# Taiwan_Arduino.net
KiCad netlist of a schematic drawn in EAGLE
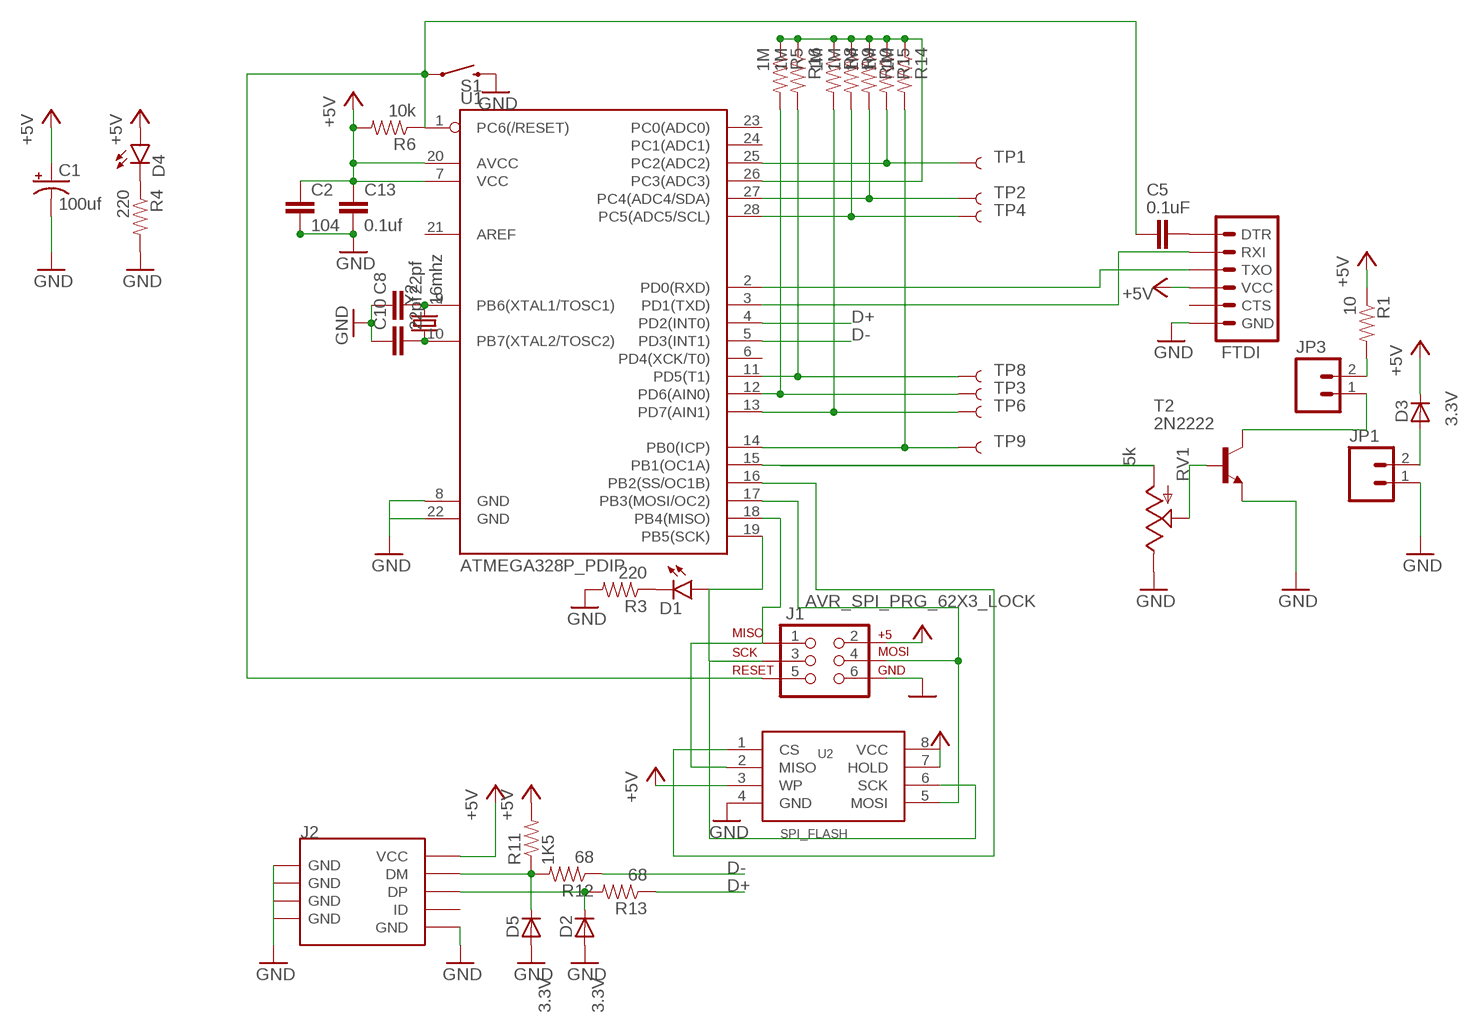
[diagram p0: schematic, sheet 1]

(export (version "E")
  (design (tool "Eeschema 10.0.6"))
  (components
    (comp (ref "C1")
      (value "100uf")
      (footprint "eagle-import:E2,5-5")
      (libsource (lib "eagle-import") (part "CPOL-USE2.5-5"))
    )
    (comp (ref "C2")
      (value "104")
      (footprint "eagle-import:CAP-PTH-5MM")
      (libsource (lib "eagle-import") (part "CAPPTH1"))
    )
    (comp (ref "C5")
      (value "0.1uF")
      (footprint "eagle-import:CAP-PTH-5MM")
      (libsource (lib "eagle-import") (part "CAPPTH1"))
    )
    (comp (ref "C8")
      (value "22pf")
      (footprint "eagle-import:CAP-PTH-5MM")
      (libsource (lib "eagle-import") (part "CAPPTH1"))
    )
    (comp (ref "C10")
      (value "22pf")
      (footprint "eagle-import:CAP-PTH-5MM")
      (libsource (lib "eagle-import") (part "CAPPTH1"))
    )
    (comp (ref "C13")
      (value "0.1uf")
      (footprint "eagle-import:CAP-PTH-5MM")
      (libsource (lib "eagle-import") (part "CAPPTH1"))
    )
    (comp (ref "D1")
      (value "LED3MM")
      (footprint "eagle-import:LED3MM")
      (libsource (lib "eagle-import") (part "LED3MM"))
    )
    (comp (ref "D2")
      (value "3.3V")
      (footprint "eagle-import:0204V")
      (libsource (lib "eagle-import") (part "DIODE-VERTDIODE_SM_VERT"))
    )
    (comp (ref "D3")
      (value "3.3V")
      (footprint "eagle-import:0204V")
      (libsource (lib "eagle-import") (part "DIODE-VERTDIODE_SM_VERT"))
    )
    (comp (ref "D4")
      (value "LED3MM")
      (footprint "eagle-import:LED3MM")
      (libsource (lib "eagle-import") (part "LED3MM"))
    )
    (comp (ref "D5")
      (value "3.3V")
      (footprint "eagle-import:0204V")
      (libsource (lib "eagle-import") (part "DIODE-VERTDIODE_SM_VERT"))
    )
    (comp (ref "FTDI")
      (value "ARDUINO_SERIAL_PROGRAMLOCK")
      (footprint "eagle-import:1X06_LOCK")
      (libsource (lib "eagle-import") (part "ARDUINO_SERIAL_PROGRAMLOCK"))
    )
    (comp (ref "J1")
      (value "AVR_SPI_PRG_62X3_LOCK")
      (footprint "eagle-import:2X3_LOCK")
      (libsource (lib "eagle-import") (part "AVR_SPI_PRG_62X3_LOCK"))
    )
    (comp (ref "J2")
      (value "USB-MINIUSB-5P-TH")
      (footprint "eagle-import:MINI-5P")
      (libsource (lib "eagle-import") (part "USB-MINIUSB-5P-TH"))
    )
    (comp (ref "JP1")
      (value "Battery")
      (footprint "eagle-import:1X02")
      (libsource (lib "eagle-import") (part "M02PTH"))
    )
    (comp (ref "JP3")
      (value "M021X02_NO_SILK")
      (footprint "eagle-import:1X02_NO_SILK")
      (libsource (lib "eagle-import") (part "M021X02_NO_SILK"))
    )
    (comp (ref "R1")
      (value "10")
      (footprint "eagle-import:AXIAL-0.1")
      (libsource (lib "eagle-import") (part "RESISTORPTH-1/4W-VERT"))
    )
    (comp (ref "R3")
      (value "220")
      (footprint "eagle-import:AXIAL-0.1")
      (libsource (lib "eagle-import") (part "RESISTORPTH-1/4W-VERT"))
    )
    (comp (ref "R4")
      (value "220")
      (footprint "eagle-import:AXIAL-0.1")
      (libsource (lib "eagle-import") (part "RESISTORPTH-1/4W-VERT"))
    )
    (comp (ref "R5")
      (value "1M")
      (footprint "eagle-import:AXIAL-0.1")
      (libsource (lib "eagle-import") (part "RESISTORPTH-1/4W-VERT"))
    )
    (comp (ref "R6")
      (value "10k")
      (footprint "eagle-import:AXIAL-0.1")
      (libsource (lib "eagle-import") (part "RESISTORPTH-1/4W-VERT"))
    )
    (comp (ref "R8")
      (value "1M")
      (footprint "eagle-import:AXIAL-0.1")
      (libsource (lib "eagle-import") (part "RESISTORPTH-1/4W-VERT"))
    )
    (comp (ref "R9")
      (value "1M")
      (footprint "eagle-import:AXIAL-0.1")
      (libsource (lib "eagle-import") (part "RESISTORPTH-1/4W-VERT"))
    )
    (comp (ref "R10")
      (value "1M")
      (footprint "eagle-import:AXIAL-0.1")
      (libsource (lib "eagle-import") (part "RESISTORPTH-1/4W-VERT"))
    )
    (comp (ref "R11")
      (value "1K5")
      (footprint "eagle-import:AXIAL-0.1")
      (libsource (lib "eagle-import") (part "RESISTORPTH-1/4W-VERT"))
    )
    (comp (ref "R12")
      (value "68")
      (footprint "eagle-import:AXIAL-0.1")
      (libsource (lib "eagle-import") (part "RESISTORPTH-1/4W-VERT"))
    )
    (comp (ref "R13")
      (value "68")
      (footprint "eagle-import:AXIAL-0.1")
      (libsource (lib "eagle-import") (part "RESISTORPTH-1/4W-VERT"))
    )
    (comp (ref "R14")
      (value "1M")
      (footprint "eagle-import:AXIAL-0.4")
      (libsource (lib "eagle-import") (part "RESISTORPTH-1/4W"))
    )
    (comp (ref "R15")
      (value "1M")
      (footprint "eagle-import:AXIAL-0.1")
      (libsource (lib "eagle-import") (part "RESISTORPTH-1/4W-VERT"))
    )
    (comp (ref "R16")
      (value "1M")
      (footprint "eagle-import:AXIAL-0.1")
      (libsource (lib "eagle-import") (part "RESISTORPTH-1/4W-VERT"))
    )
    (comp (ref "RV1")
      (value "5k")
      (footprint "eagle-import:ALPS_POT")
      (libsource (lib "eagle-import") (part "POT"))
    )
    (comp (ref "S1")
      (value "SWITCH-MOMENTARY-2PTH")
      (footprint "eagle-import:TACTILE-PTH")
      (libsource (lib "eagle-import") (part "SWITCH-MOMENTARY-2PTH"))
    )
    (comp (ref "T2")
      (value "2N2222")
      (footprint "eagle-import:TO92-EBC-OVAL")
      (libsource (lib "eagle-import") (part "2N2222"))
    )
    (comp (ref "TP1")
      (value "TEST-POINT")
      (footprint "eagle-import:PADBIG")
      (libsource (lib "eagle-import") (part "TEST-POINT"))
    )
    (comp (ref "TP2")
      (value "TEST-POINT")
      (footprint "eagle-import:PADBIG")
      (libsource (lib "eagle-import") (part "TEST-POINT"))
    )
    (comp (ref "TP3")
      (value "TEST-POINT")
      (footprint "eagle-import:PADBIG")
      (libsource (lib "eagle-import") (part "TEST-POINT"))
    )
    (comp (ref "TP4")
      (value "TEST-POINT")
      (footprint "eagle-import:PADBIG")
      (libsource (lib "eagle-import") (part "TEST-POINT"))
    )
    (comp (ref "TP6")
      (value "TEST-POINT")
      (footprint "eagle-import:PADBIG")
      (libsource (lib "eagle-import") (part "TEST-POINT"))
    )
    (comp (ref "TP8")
      (value "TEST-POINT")
      (footprint "eagle-import:PADBIG")
      (libsource (lib "eagle-import") (part "TEST-POINT"))
    )
    (comp (ref "TP9")
      (value "TEST-POINT")
      (footprint "eagle-import:PADBIG")
      (libsource (lib "eagle-import") (part "TEST-POINT"))
    )
    (comp (ref "U1")
      (value "ATMEGA328P_PDIP")
      (footprint "eagle-import:DIL28-3")
      (libsource (lib "eagle-import") (part "ATMEGA328P_PDIP"))
    )
    (comp (ref "U2")
      (value "SPI_FLASH")
      (footprint "eagle-import:DIL08")
      (libsource (lib "eagle-import") (part "SPI_FLASH-X25XX"))
    )
    (comp (ref "Y2")
      (value "16mhz")
      (footprint "eagle-import:HC49U-V")
      (libsource (lib "eagle-import") (part "CRYSTALHC49UV"))
    )
  )
  (nets
    (net (code "1") (name "+5V") (class "Default")
      (node (ref "C1") (pin "+") (pinfunction "+_+") (pintype "passive"))
      (node (ref "C13") (pin "1") (pinfunction "1_1") (pintype "passive"))
      (node (ref "C2") (pin "1") (pinfunction "1_1") (pintype "passive"))
      (node (ref "D3") (pin "2") (pinfunction "C_2") (pintype "passive"))
      (node (ref "D4") (pin "A") (pinfunction "A_A") (pintype "passive"))
      (node (ref "FTDI") (pin "4") (pinfunction "VCC_4") (pintype "passive"))
      (node (ref "J1") (pin "2") (pinfunction "2_2") (pintype "passive"))
      (node (ref "J2") (pin "VCC") (pinfunction "VCC_VCC") (pintype "bidirectional"))
      (node (ref "R1") (pin "P$1") (pinfunction "1_P$1") (pintype "passive"))
      (node (ref "R11") (pin "P$2") (pinfunction "2_P$2") (pintype "passive"))
      (node (ref "R6") (pin "P$2") (pinfunction "2_P$2") (pintype "passive"))
      (node (ref "U1") (pin "20") (pinfunction "AVCC_20") (pintype "bidirectional"))
      (node (ref "U1") (pin "7") (pinfunction "VCC_7") (pintype "bidirectional"))
      (node (ref "U2") (pin "3") (pinfunction "WP_3") (pintype "bidirectional"))
      (node (ref "U2") (pin "7") (pinfunction "HOLD_7") (pintype "bidirectional"))
      (node (ref "U2") (pin "8") (pinfunction "VCC_8") (pintype "bidirectional"))
    )
    (net (code "2") (name "/D+") (class "Default")
      (node (ref "R13") (pin "P$1") (pinfunction "1_P$1") (pintype "passive"))
      (node (ref "U1") (pin "4") (pinfunction "PD2(INT0)_4") (pintype "bidirectional"))
    )
    (net (code "3") (name "/D-") (class "Default")
      (node (ref "R12") (pin "P$1") (pinfunction "1_P$1") (pintype "passive"))
      (node (ref "U1") (pin "5") (pinfunction "PD3(INT1)_5") (pintype "bidirectional"))
    )
    (net (code "4") (name "GND") (class "Default")
      (node (ref "C1") (pin "-") (pinfunction "-_-") (pintype "passive"))
      (node (ref "C10") (pin "1") (pinfunction "1_1") (pintype "passive"))
      (node (ref "C13") (pin "2") (pinfunction "2_2") (pintype "passive"))
      (node (ref "C2") (pin "2") (pinfunction "2_2") (pintype "passive"))
      (node (ref "C8") (pin "1") (pinfunction "1_1") (pintype "passive"))
      (node (ref "D2") (pin "1") (pinfunction "A_1") (pintype "passive"))
      (node (ref "D5") (pin "1") (pinfunction "A_1") (pintype "passive"))
      (node (ref "FTDI") (pin "6") (pinfunction "GND_6") (pintype "passive"))
      (node (ref "J1") (pin "6") (pinfunction "6_6") (pintype "passive"))
      (node (ref "J2") (pin "GND") (pinfunction "GND_GND") (pintype "bidirectional"))
      (node (ref "J2") (pin "S1") (pinfunction "GND_S1") (pintype "bidirectional"))
      (node (ref "J2") (pin "S2") (pinfunction "GND_S2") (pintype "bidirectional"))
      (node (ref "J2") (pin "S3") (pinfunction "GND_S3") (pintype "bidirectional"))
      (node (ref "J2") (pin "S4") (pinfunction "GND_S4") (pintype "bidirectional"))
      (node (ref "JP1") (pin "1") (pinfunction "1_1") (pintype "passive"))
      (node (ref "R3") (pin "P$2") (pinfunction "2_P$2") (pintype "passive"))
      (node (ref "R4") (pin "P$2") (pinfunction "2_P$2") (pintype "passive"))
      (node (ref "RV1") (pin "P$1") (pinfunction "E_P$1") (pintype "passive"))
      (node (ref "S1") (pin "3") (pinfunction "2_3") (pintype "passive"))
      (node (ref "T2") (pin "E") (pinfunction "E_E") (pintype "passive"))
      (node (ref "U1") (pin "22") (pinfunction "GND_22") (pintype "bidirectional"))
      (node (ref "U1") (pin "8") (pinfunction "GND_8") (pintype "bidirectional"))
      (node (ref "U2") (pin "4") (pinfunction "GND_4") (pintype "bidirectional"))
    )
    (net (code "5") (name "Net-(D1-C)") (class "Default")
      (node (ref "D1") (pin "K") (pinfunction "C_K") (pintype "passive"))
      (node (ref "R3") (pin "P$1") (pinfunction "1_P$1") (pintype "passive"))
    )
    (net (code "6") (name "Net-(D2-C)") (class "Default")
      (node (ref "D2") (pin "2") (pinfunction "C_2") (pintype "passive"))
      (node (ref "J2") (pin "DP") (pinfunction "DP_DP") (pintype "bidirectional"))
      (node (ref "R13") (pin "P$2") (pinfunction "2_P$2") (pintype "passive"))
    )
    (net (code "7") (name "Net-(D3-A)") (class "Default")
      (node (ref "D3") (pin "1") (pinfunction "A_1") (pintype "passive"))
      (node (ref "JP1") (pin "2") (pinfunction "2_2") (pintype "passive"))
    )
    (net (code "8") (name "Net-(D4-C)") (class "Default")
      (node (ref "D4") (pin "K") (pinfunction "C_K") (pintype "passive"))
      (node (ref "R4") (pin "P$1") (pinfunction "1_P$1") (pintype "passive"))
    )
    (net (code "9") (name "Net-(D5-C)") (class "Default")
      (node (ref "D5") (pin "2") (pinfunction "C_2") (pintype "passive"))
      (node (ref "J2") (pin "DM") (pinfunction "DM_DM") (pintype "bidirectional"))
      (node (ref "R11") (pin "P$1") (pinfunction "1_P$1") (pintype "passive"))
      (node (ref "R12") (pin "P$2") (pinfunction "2_P$2") (pintype "passive"))
    )
    (net (code "10") (name "Net-(FTDI-DTR)") (class "Default")
      (node (ref "C5") (pin "2") (pinfunction "2_2") (pintype "passive"))
      (node (ref "FTDI") (pin "1") (pinfunction "DTR_1") (pintype "passive"))
    )
    (net (code "11") (name "Net-(FTDI-RXI)") (class "Default")
      (node (ref "FTDI") (pin "2") (pinfunction "RXI_2") (pintype "passive"))
      (node (ref "U1") (pin "3") (pinfunction "PD1(TXD)_3") (pintype "bidirectional"))
    )
    (net (code "12") (name "Net-(FTDI-TXO)") (class "Default")
      (node (ref "FTDI") (pin "3") (pinfunction "TXO_3") (pintype "passive"))
      (node (ref "U1") (pin "2") (pinfunction "PD0(RXD)_2") (pintype "bidirectional"))
    )
    (net (code "13") (name "Net-(JP3-Pad1)") (class "Default")
      (node (ref "JP3") (pin "1") (pinfunction "1_1") (pintype "passive"))
      (node (ref "T2") (pin "C") (pinfunction "C_C") (pintype "passive"))
    )
    (net (code "14") (name "Net-(R1-2)") (class "Default")
      (node (ref "JP3") (pin "2") (pinfunction "2_2") (pintype "passive"))
      (node (ref "R1") (pin "P$2") (pinfunction "2_P$2") (pintype "passive"))
    )
    (net (code "15") (name "Net-(R5-2)") (class "Default")
      (node (ref "R5") (pin "P$2") (pinfunction "2_P$2") (pintype "passive"))
      (node (ref "TP3") (pin "P$1") (pinfunction "1_P$1") (pintype "bidirectional"))
      (node (ref "U1") (pin "12") (pinfunction "PD6(AIN0)_12") (pintype "bidirectional"))
    )
    (net (code "16") (name "Net-(R6-1)") (class "Default")
      (node (ref "C5") (pin "1") (pinfunction "1_1") (pintype "passive"))
      (node (ref "J1") (pin "5") (pinfunction "5_5") (pintype "passive"))
      (node (ref "R6") (pin "P$1") (pinfunction "1_P$1") (pintype "passive"))
      (node (ref "S1") (pin "1") (pinfunction "1_1") (pintype "passive"))
      (node (ref "U1") (pin "1") (pinfunction "PC6(/RESET)_1") (pintype "bidirectional"))
    )
    (net (code "17") (name "Net-(R8-2)") (class "Default")
      (node (ref "R8") (pin "P$2") (pinfunction "2_P$2") (pintype "passive"))
      (node (ref "TP6") (pin "P$1") (pinfunction "1_P$1") (pintype "bidirectional"))
      (node (ref "U1") (pin "13") (pinfunction "PD7(AIN1)_13") (pintype "bidirectional"))
    )
    (net (code "18") (name "Net-(R9-2)") (class "Default")
      (node (ref "R9") (pin "P$2") (pinfunction "2_P$2") (pintype "passive"))
      (node (ref "TP4") (pin "P$1") (pinfunction "1_P$1") (pintype "bidirectional"))
      (node (ref "U1") (pin "28") (pinfunction "PC5(ADC5/SCL)_28") (pintype "bidirectional"))
    )
    (net (code "19") (name "Net-(R10-1)") (class "Default")
      (node (ref "R10") (pin "P$1") (pinfunction "1_P$1") (pintype "passive"))
      (node (ref "R14") (pin "P$1") (pinfunction "1_P$1") (pintype "passive"))
      (node (ref "R15") (pin "P$1") (pinfunction "1_P$1") (pintype "passive"))
      (node (ref "R16") (pin "P$1") (pinfunction "1_P$1") (pintype "passive"))
      (node (ref "R5") (pin "P$1") (pinfunction "1_P$1") (pintype "passive"))
      (node (ref "R8") (pin "P$1") (pinfunction "1_P$1") (pintype "passive"))
      (node (ref "R9") (pin "P$1") (pinfunction "1_P$1") (pintype "passive"))
      (node (ref "U1") (pin "26") (pinfunction "PC3(ADC3)_26") (pintype "bidirectional"))
    )
    (net (code "20") (name "Net-(R10-2)") (class "Default")
      (node (ref "R10") (pin "P$2") (pinfunction "2_P$2") (pintype "passive"))
      (node (ref "TP2") (pin "P$1") (pinfunction "1_P$1") (pintype "bidirectional"))
      (node (ref "U1") (pin "27") (pinfunction "PC4(ADC4/SDA)_27") (pintype "bidirectional"))
    )
    (net (code "21") (name "Net-(R14-2)") (class "Default")
      (node (ref "R14") (pin "P$2") (pinfunction "2_P$2") (pintype "passive"))
      (node (ref "TP9") (pin "P$1") (pinfunction "1_P$1") (pintype "bidirectional"))
      (node (ref "U1") (pin "14") (pinfunction "PB0(ICP)_14") (pintype "bidirectional"))
    )
    (net (code "22") (name "Net-(R15-2)") (class "Default")
      (node (ref "R15") (pin "P$2") (pinfunction "2_P$2") (pintype "passive"))
      (node (ref "TP1") (pin "P$1") (pinfunction "1_P$1") (pintype "bidirectional"))
      (node (ref "U1") (pin "25") (pinfunction "PC2(ADC2)_25") (pintype "bidirectional"))
    )
    (net (code "23") (name "Net-(R16-2)") (class "Default")
      (node (ref "R16") (pin "P$2") (pinfunction "2_P$2") (pintype "passive"))
      (node (ref "TP8") (pin "P$1") (pinfunction "1_P$1") (pintype "bidirectional"))
      (node (ref "U1") (pin "11") (pinfunction "PD5(T1)_11") (pintype "bidirectional"))
    )
    (net (code "24") (name "Net-(RV1-A)") (class "Default")
      (node (ref "RV1") (pin "P$3") (pinfunction "A_P$3") (pintype "passive"))
      (node (ref "U1") (pin "15") (pinfunction "PB1(OC1A)_15") (pintype "bidirectional"))
    )
    (net (code "25") (name "Net-(RV1-S)") (class "Default")
      (node (ref "RV1") (pin "P$2") (pinfunction "S_P$2") (pintype "passive"))
      (node (ref "T2") (pin "B") (pinfunction "B_B") (pintype "passive"))
    )
    (net (code "26") (name "Net-(U1-PB2(SS{slash}OC1B))") (class "Default")
      (node (ref "U1") (pin "16") (pinfunction "PB2(SS/OC1B)_16") (pintype "bidirectional"))
      (node (ref "U2") (pin "1") (pinfunction "CS_1") (pintype "bidirectional"))
    )
    (net (code "27") (name "Net-(U1-PB3(MOSI{slash}OC2))") (class "Default")
      (node (ref "J1") (pin "4") (pinfunction "4_4") (pintype "passive"))
      (node (ref "U1") (pin "17") (pinfunction "PB3(MOSI/OC2)_17") (pintype "bidirectional"))
      (node (ref "U2") (pin "5") (pinfunction "MOSI_5") (pintype "bidirectional"))
    )
    (net (code "28") (name "Net-(U1-PB4(MISO))") (class "Default")
      (node (ref "J1") (pin "1") (pinfunction "1_1") (pintype "passive"))
      (node (ref "U1") (pin "18") (pinfunction "PB4(MISO)_18") (pintype "bidirectional"))
      (node (ref "U2") (pin "2") (pinfunction "MISO_2") (pintype "bidirectional"))
    )
    (net (code "29") (name "Net-(U1-PB5(SCK))") (class "Default")
      (node (ref "D1") (pin "A") (pinfunction "A_A") (pintype "passive"))
      (node (ref "J1") (pin "3") (pinfunction "3_3") (pintype "passive"))
      (node (ref "U1") (pin "19") (pinfunction "PB5(SCK)_19") (pintype "bidirectional"))
      (node (ref "U2") (pin "6") (pinfunction "SCK_6") (pintype "bidirectional"))
    )
    (net (code "30") (name "Net-(U1-PB6(XTAL1{slash}TOSC1))") (class "Default")
      (node (ref "C8") (pin "2") (pinfunction "2_2") (pintype "passive"))
      (node (ref "U1") (pin "9") (pinfunction "PB6(XTAL1/TOSC1)_9") (pintype "bidirectional"))
      (node (ref "Y2") (pin "2") (pinfunction "2_2") (pintype "passive"))
    )
    (net (code "31") (name "Net-(U1-PB7(XTAL2{slash}TOSC2))") (class "Default")
      (node (ref "C10") (pin "2") (pinfunction "2_2") (pintype "passive"))
      (node (ref "U1") (pin "10") (pinfunction "PB7(XTAL2/TOSC2)_10") (pintype "bidirectional"))
      (node (ref "Y2") (pin "1") (pinfunction "1_1") (pintype "passive"))
    )
    (net (code "32") (name "unconnected-(FTDI-CTS-Pad5)") (class "Default")
      (node (ref "FTDI") (pin "5") (pinfunction "CTS_5") (pintype "passive"))
    )
    (net (code "33") (name "unconnected-(J2-PadID)") (class "Default")
      (node (ref "J2") (pin "ID") (pinfunction "ID_ID") (pintype "bidirectional"))
    )
    (net (code "34") (name "unconnected-(U1-AREF-Pad21)") (class "Default")
      (node (ref "U1") (pin "21") (pinfunction "AREF_21") (pintype "bidirectional"))
    )
    (net (code "35") (name "unconnected-(U1-PC0(ADC0)-Pad23)") (class "Default")
      (node (ref "U1") (pin "23") (pinfunction "PC0(ADC0)_23") (pintype "bidirectional"))
    )
    (net (code "36") (name "unconnected-(U1-PC1(ADC1)-Pad24)") (class "Default")
      (node (ref "U1") (pin "24") (pinfunction "PC1(ADC1)_24") (pintype "bidirectional"))
    )
    (net (code "37") (name "unconnected-(U1-PD4(XCK{slash}T0)-Pad6)") (class "Default")
      (node (ref "U1") (pin "6") (pinfunction "PD4(XCK/T0)_6") (pintype "bidirectional"))
    )
  )
)
